# easyeda-caudalimetro.net
KiCad netlist of a schematic drawn in EasyEDA
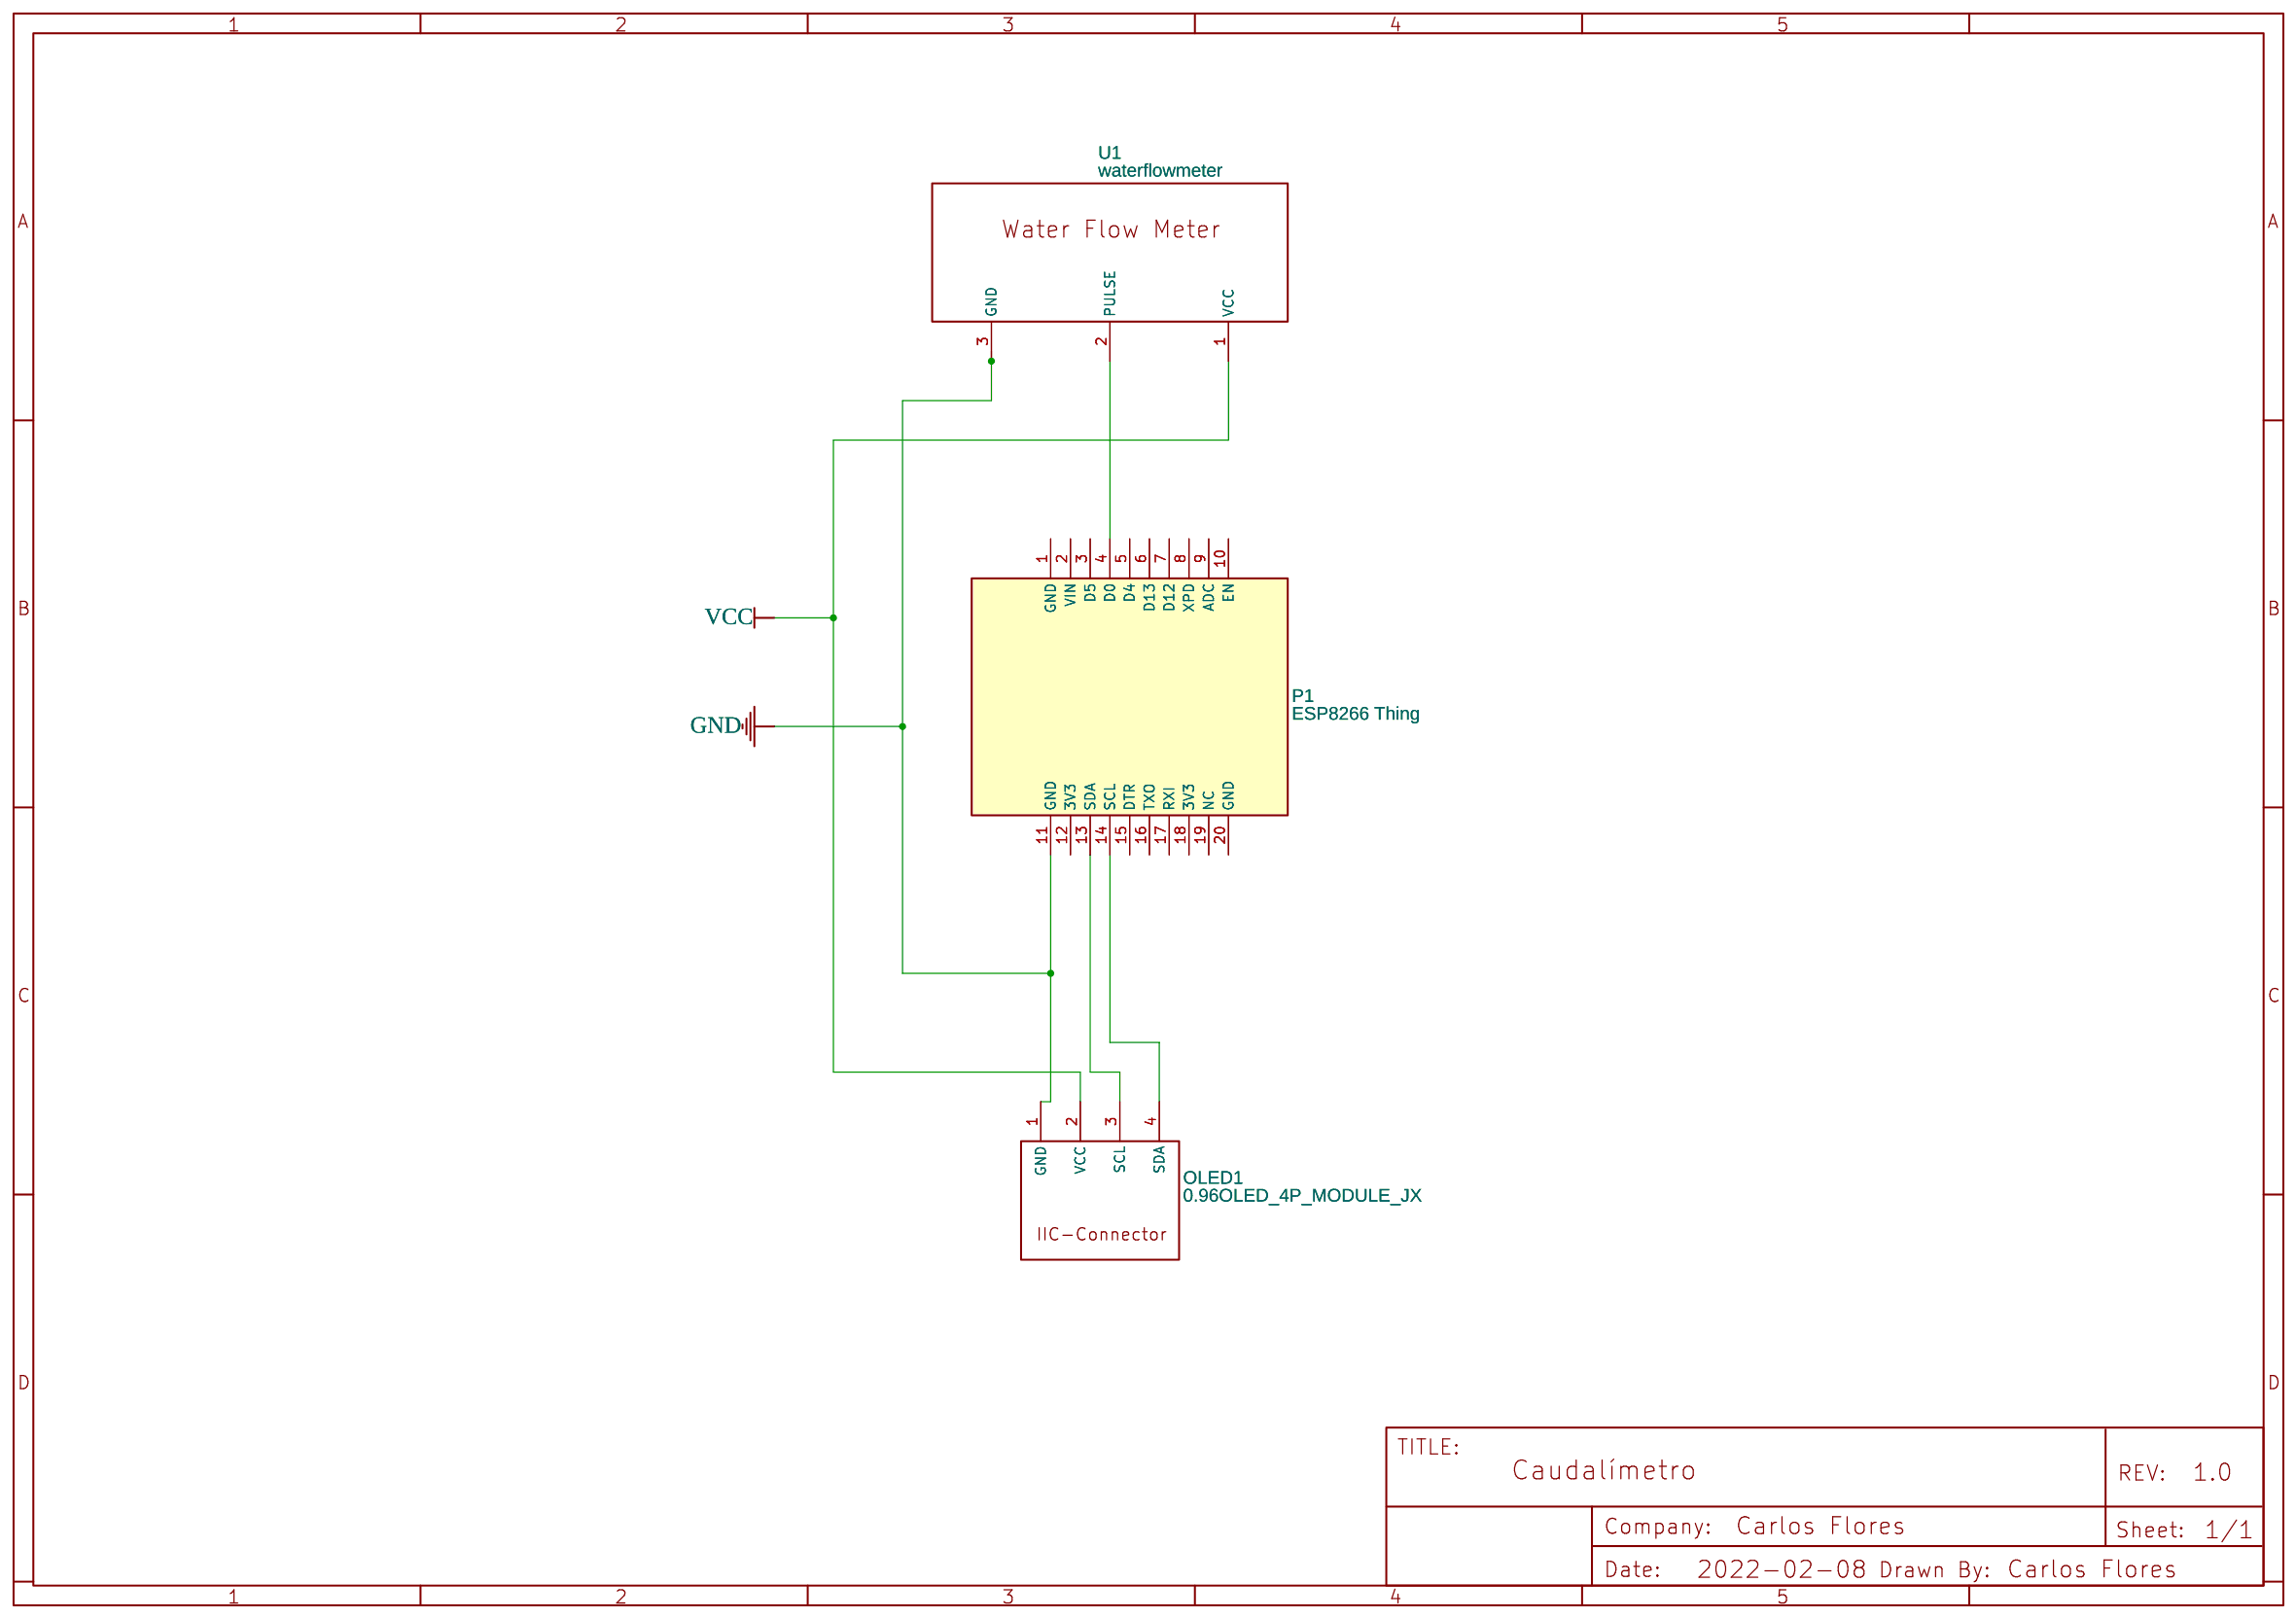
[diagram p0: schematic sheet]

(export (version "E")
  (design (tool "Eeschema 10.0.6"))
  (components
    (comp (ref "OLED1")
      (value "0.96OLED_4P_MODULE_JX")
      (fields (field (name "BOM_Supplier Part") "C9900004566"))
      (libsource (lib "") (part "0.96OLED_4P_MODULE_JX"))
    )
    (comp (ref "P1") (value "ESP8266 Thing") (libsource (lib "") (part "ESP8266 Thing")))
    (comp (ref "U1")
      (value "waterflowmeter")
      (fields (field (name "BOM_Manufacturer Part") "all"))
      (libsource (lib "") (part "waterflowmeter"))
    )
  )
  (nets
    (net (code "1") (name "GND") (class "Default")
      (node (ref "OLED1") (pin "1") (pinfunction "GND_1") (pintype "unspecified"))
      (node (ref "P1") (pin "11") (pinfunction "GND_11") (pintype "unspecified"))
      (node (ref "U1") (pin "3") (pinfunction "GND_3") (pintype "unspecified"))
    )
    (net (code "2") (name "Net-(OLED1-SCL)") (class "Default")
      (node (ref "OLED1") (pin "3") (pinfunction "SCL_3") (pintype "unspecified"))
      (node (ref "P1") (pin "13") (pinfunction "SDA_13") (pintype "unspecified"))
    )
    (net (code "3") (name "Net-(OLED1-SDA)") (class "Default")
      (node (ref "OLED1") (pin "4") (pinfunction "SDA_4") (pintype "unspecified"))
      (node (ref "P1") (pin "14") (pinfunction "SCL_14") (pintype "unspecified"))
    )
    (net (code "4") (name "Net-(P1-D0)") (class "Default")
      (node (ref "P1") (pin "4") (pinfunction "D0_4") (pintype "unspecified"))
      (node (ref "U1") (pin "2") (pinfunction "PULSE_2") (pintype "unspecified"))
    )
    (net (code "5") (name "VCC") (class "Default")
      (node (ref "OLED1") (pin "2") (pinfunction "VCC_2") (pintype "unspecified"))
      (node (ref "U1") (pin "1") (pinfunction "VCC_1") (pintype "unspecified"))
    )
    (net (code "6") (name "unconnected-(P1-3V3-Pad12)") (class "Default")
      (node (ref "P1") (pin "12") (pinfunction "3V3_12") (pintype "unspecified"))
    )
    (net (code "7") (name "unconnected-(P1-3V3-Pad18)") (class "Default")
      (node (ref "P1") (pin "18") (pinfunction "3V3_18") (pintype "unspecified"))
    )
    (net (code "8") (name "unconnected-(P1-ADC-Pad9)") (class "Default")
      (node (ref "P1") (pin "9") (pinfunction "ADC_9") (pintype "unspecified"))
    )
    (net (code "9") (name "unconnected-(P1-D4-Pad5)") (class "Default")
      (node (ref "P1") (pin "5") (pinfunction "D4_5") (pintype "unspecified"))
    )
    (net (code "10") (name "unconnected-(P1-D5-Pad3)") (class "Default")
      (node (ref "P1") (pin "3") (pinfunction "D5_3") (pintype "unspecified"))
    )
    (net (code "11") (name "unconnected-(P1-D12-Pad7)") (class "Default")
      (node (ref "P1") (pin "7") (pinfunction "D12_7") (pintype "unspecified"))
    )
    (net (code "12") (name "unconnected-(P1-D13-Pad6)") (class "Default")
      (node (ref "P1") (pin "6") (pinfunction "D13_6") (pintype "unspecified"))
    )
    (net (code "13") (name "unconnected-(P1-DTR-Pad15)") (class "Default")
      (node (ref "P1") (pin "15") (pinfunction "DTR_15") (pintype "unspecified"))
    )
    (net (code "14") (name "unconnected-(P1-EN-Pad10)") (class "Default")
      (node (ref "P1") (pin "10") (pinfunction "EN_10") (pintype "unspecified"))
    )
    (net (code "15") (name "unconnected-(P1-GND-Pad1)") (class "Default")
      (node (ref "P1") (pin "1") (pinfunction "GND_1") (pintype "unspecified"))
    )
    (net (code "16") (name "unconnected-(P1-GND-Pad20)") (class "Default")
      (node (ref "P1") (pin "20") (pinfunction "GND_20") (pintype "unspecified"))
    )
    (net (code "17") (name "unconnected-(P1-NC-Pad19)") (class "Default")
      (node (ref "P1") (pin "19") (pinfunction "NC_19") (pintype "unspecified"))
    )
    (net (code "18") (name "unconnected-(P1-RXI-Pad17)") (class "Default")
      (node (ref "P1") (pin "17") (pinfunction "RXI_17") (pintype "unspecified"))
    )
    (net (code "19") (name "unconnected-(P1-TXO-Pad16)") (class "Default")
      (node (ref "P1") (pin "16") (pinfunction "TXO_16") (pintype "unspecified"))
    )
    (net (code "20") (name "unconnected-(P1-VIN-Pad2)") (class "Default")
      (node (ref "P1") (pin "2") (pinfunction "VIN_2") (pintype "unspecified"))
    )
    (net (code "21") (name "unconnected-(P1-XPD-Pad8)") (class "Default")
      (node (ref "P1") (pin "8") (pinfunction "XPD_8") (pintype "unspecified"))
    )
  )
)
